# lightswitchx1.net
KiCad netlist of a schematic drawn in EAGLE
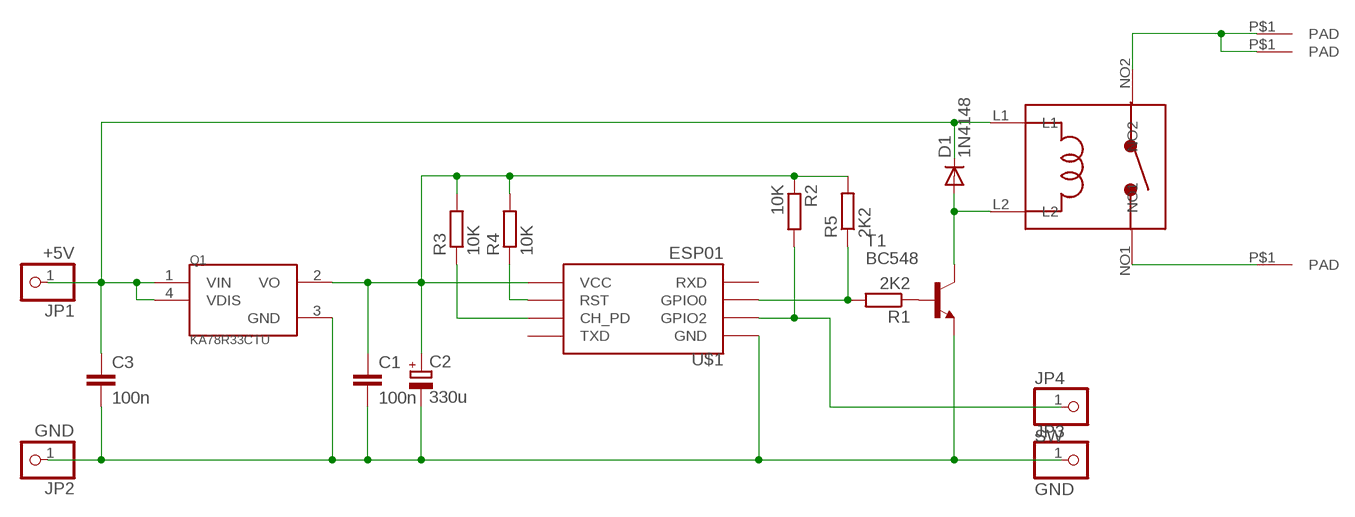
[diagram p0: schematic, sheet 1]

(export (version "E")
  (design (tool "Eeschema 10.0.6"))
  (components
    (comp (ref "C1")
      (value "100n")
      (footprint "eagle-import:C025-030X050")
      (libsource (lib "eagle-import") (part "C-EU025-030X050"))
    )
    (comp (ref "C2")
      (value "330u")
      (footprint "eagle-import:E2-5")
      (libsource (lib "eagle-import") (part "CPOL-EUE2-5"))
    )
    (comp (ref "C3")
      (value "100n")
      (footprint "eagle-import:C025-030X050")
      (libsource (lib "eagle-import") (part "C-EU025-030X050"))
    )
    (comp (ref "D1")
      (value "1N4148")
      (footprint "eagle-import:DO35-7")
      (libsource (lib "eagle-import") (part "1N4148DO35-7"))
    )
    (comp (ref "JP1")
      (value "+5V")
      (footprint "eagle-import:1X01")
      (libsource (lib "eagle-import") (part "PINHD-1X1"))
    )
    (comp (ref "JP2")
      (value "GND")
      (footprint "eagle-import:1X01")
      (libsource (lib "eagle-import") (part "PINHD-1X1"))
    )
    (comp (ref "JP3")
      (value "GND")
      (footprint "eagle-import:1X01")
      (libsource (lib "eagle-import") (part "PINHD-1X1"))
    )
    (comp (ref "JP4")
      (value "SW")
      (footprint "eagle-import:1X01")
      (libsource (lib "eagle-import") (part "PINHD-1X1"))
    )
    (comp (ref "Q1")
      (value "KA78R33CTU")
      (footprint "eagle-import:TO-220-4")
      (fields (field (name "MF") "Fairchild Semiconductor"))
      (libsource (lib "eagle-import") (part "KA78R33CTU"))
    )
    (comp (ref "R1")
      (value "2K2")
      (footprint "eagle-import:0207_10")
      (libsource (lib "eagle-import") (part "R-EU_0207/10"))
    )
    (comp (ref "R2")
      (value "10K")
      (footprint "eagle-import:0207_10")
      (libsource (lib "eagle-import") (part "R-EU_0207/10"))
    )
    (comp (ref "R3")
      (value "10K")
      (footprint "eagle-import:0207_10")
      (libsource (lib "eagle-import") (part "R-EU_0207/10"))
    )
    (comp (ref "R4")
      (value "10K")
      (footprint "eagle-import:0207_10")
      (libsource (lib "eagle-import") (part "R-EU_0207/10"))
    )
    (comp (ref "R5")
      (value "2K2")
      (footprint "eagle-import:0207_10")
      (libsource (lib "eagle-import") (part "R-EU_0207/10"))
    )
    (comp (ref "T1")
      (value "BC548")
      (footprint "eagle-import:TO92")
      (libsource (lib "eagle-import") (part "BC547"))
    )
    (comp (ref "U$1")
      (value "ESP01")
      (footprint "eagle-import:ESP01")
      (libsource (lib "eagle-import") (part "ESP01"))
    )
    (comp (ref "U$2")
      (value "LEG1A-5")
      (footprint "eagle-import:LEG-1A-5")
      (libsource (lib "eagle-import") (part "LEG1A-5"))
    )
    (comp (ref "U$3")
      (value "PAD")
      (footprint "eagle-import:PAD")
      (libsource (lib "eagle-import") (part "PAD"))
    )
    (comp (ref "U$4")
      (value "PAD")
      (footprint "eagle-import:PAD")
      (libsource (lib "eagle-import") (part "PAD"))
    )
    (comp (ref "U$5")
      (value "PAD")
      (footprint "eagle-import:PAD")
      (libsource (lib "eagle-import") (part "PAD"))
    )
  )
  (nets
    (net (code "1") (name "Net-(JP4-Pad1)") (class "Default")
      (node (ref "JP4") (pin "1") (pinfunction "1_1") (pintype "passive"))
      (node (ref "R2") (pin "2") (pinfunction "2_2") (pintype "passive"))
      (node (ref "U$1") (pin "GPIO2") (pinfunction "GPIO2_GPIO2") (pintype "bidirectional"))
    )
    (net (code "2") (name "Net-(Q1-GND)") (class "Default")
      (node (ref "C1") (pin "2") (pinfunction "2_2") (pintype "passive"))
      (node (ref "C2") (pin "-") (pinfunction "-_-") (pintype "passive"))
      (node (ref "C3") (pin "2") (pinfunction "2_2") (pintype "passive"))
      (node (ref "JP2") (pin "1") (pinfunction "1_1") (pintype "passive"))
      (node (ref "JP3") (pin "1") (pinfunction "1_1") (pintype "passive"))
      (node (ref "Q1") (pin "3") (pinfunction "GND_3") (pintype "passive"))
      (node (ref "T1") (pin "1") (pinfunction "E_1") (pintype "passive"))
      (node (ref "U$1") (pin "GND") (pinfunction "GND_GND") (pintype "bidirectional"))
    )
    (net (code "3") (name "Net-(Q1-VDIS)") (class "Default")
      (node (ref "C3") (pin "1") (pinfunction "1_1") (pintype "passive"))
      (node (ref "D1") (pin "C") (pinfunction "C_C") (pintype "passive"))
      (node (ref "JP1") (pin "1") (pinfunction "1_1") (pintype "passive"))
      (node (ref "Q1") (pin "1") (pinfunction "VIN_1") (pintype "input"))
      (node (ref "Q1") (pin "4") (pinfunction "VDIS_4") (pintype "passive"))
      (node (ref "U$2") (pin "L1") (pinfunction "L1_L1") (pintype "bidirectional"))
    )
    (net (code "4") (name "Net-(Q1-VO)") (class "Default")
      (node (ref "C1") (pin "1") (pinfunction "1_1") (pintype "passive"))
      (node (ref "C2") (pin "+") (pinfunction "+_+") (pintype "passive"))
      (node (ref "Q1") (pin "2") (pinfunction "VO_2") (pintype "output"))
      (node (ref "R2") (pin "1") (pinfunction "1_1") (pintype "passive"))
      (node (ref "R3") (pin "2") (pinfunction "2_2") (pintype "passive"))
      (node (ref "R4") (pin "2") (pinfunction "2_2") (pintype "passive"))
      (node (ref "R5") (pin "2") (pinfunction "2_2") (pintype "passive"))
      (node (ref "U$1") (pin "VCC") (pinfunction "VCC_VCC") (pintype "bidirectional"))
    )
    (net (code "5") (name "Net-(R1-Pad2)") (class "Default")
      (node (ref "R1") (pin "2") (pinfunction "2_2") (pintype "passive"))
      (node (ref "R5") (pin "1") (pinfunction "1_1") (pintype "passive"))
      (node (ref "U$1") (pin "GPIO0") (pinfunction "GPIO0_GPIO0") (pintype "bidirectional"))
    )
    (net (code "6") (name "Net-(R3-Pad1)") (class "Default")
      (node (ref "R3") (pin "1") (pinfunction "1_1") (pintype "passive"))
      (node (ref "U$1") (pin "CH_PD") (pinfunction "CH_PD_CH_PD") (pintype "bidirectional"))
    )
    (net (code "7") (name "Net-(R4-Pad1)") (class "Default")
      (node (ref "R4") (pin "1") (pinfunction "1_1") (pintype "passive"))
      (node (ref "U$1") (pin "RST") (pinfunction "RST_RST") (pintype "bidirectional"))
    )
    (net (code "8") (name "Net-(T1-B)") (class "Default")
      (node (ref "R1") (pin "1") (pinfunction "1_1") (pintype "passive"))
      (node (ref "T1") (pin "2") (pinfunction "B_2") (pintype "passive"))
    )
    (net (code "9") (name "Net-(T1-C)") (class "Default")
      (node (ref "D1") (pin "A") (pinfunction "A_A") (pintype "passive"))
      (node (ref "T1") (pin "3") (pinfunction "C_3") (pintype "passive"))
      (node (ref "U$2") (pin "L2") (pinfunction "L2_L2") (pintype "bidirectional"))
    )
    (net (code "10") (name "Net-(U$3-PAD)") (class "Default")
      (node (ref "U$2") (pin "NO2") (pinfunction "NO2_NO2") (pintype "bidirectional"))
      (node (ref "U$3") (pin "P$1") (pinfunction "PAD_P$1") (pintype "bidirectional"))
      (node (ref "U$5") (pin "P$1") (pinfunction "PAD_P$1") (pintype "bidirectional"))
    )
    (net (code "11") (name "Net-(U$4-PAD)") (class "Default")
      (node (ref "U$2") (pin "NO1") (pinfunction "NO1_NO1") (pintype "bidirectional"))
      (node (ref "U$4") (pin "P$1") (pinfunction "PAD_P$1") (pintype "bidirectional"))
    )
    (net (code "12") (name "unconnected-(U$1-RXD-PadRX)") (class "Default")
      (node (ref "U$1") (pin "RX") (pinfunction "RXD_RX") (pintype "bidirectional"))
    )
    (net (code "13") (name "unconnected-(U$1-TXD-PadTX)") (class "Default")
      (node (ref "U$1") (pin "TX") (pinfunction "TXD_TX") (pintype "bidirectional"))
    )
  )
)
